# picobug.net
KiCad netlist of a schematic drawn in EasyEDA Pro
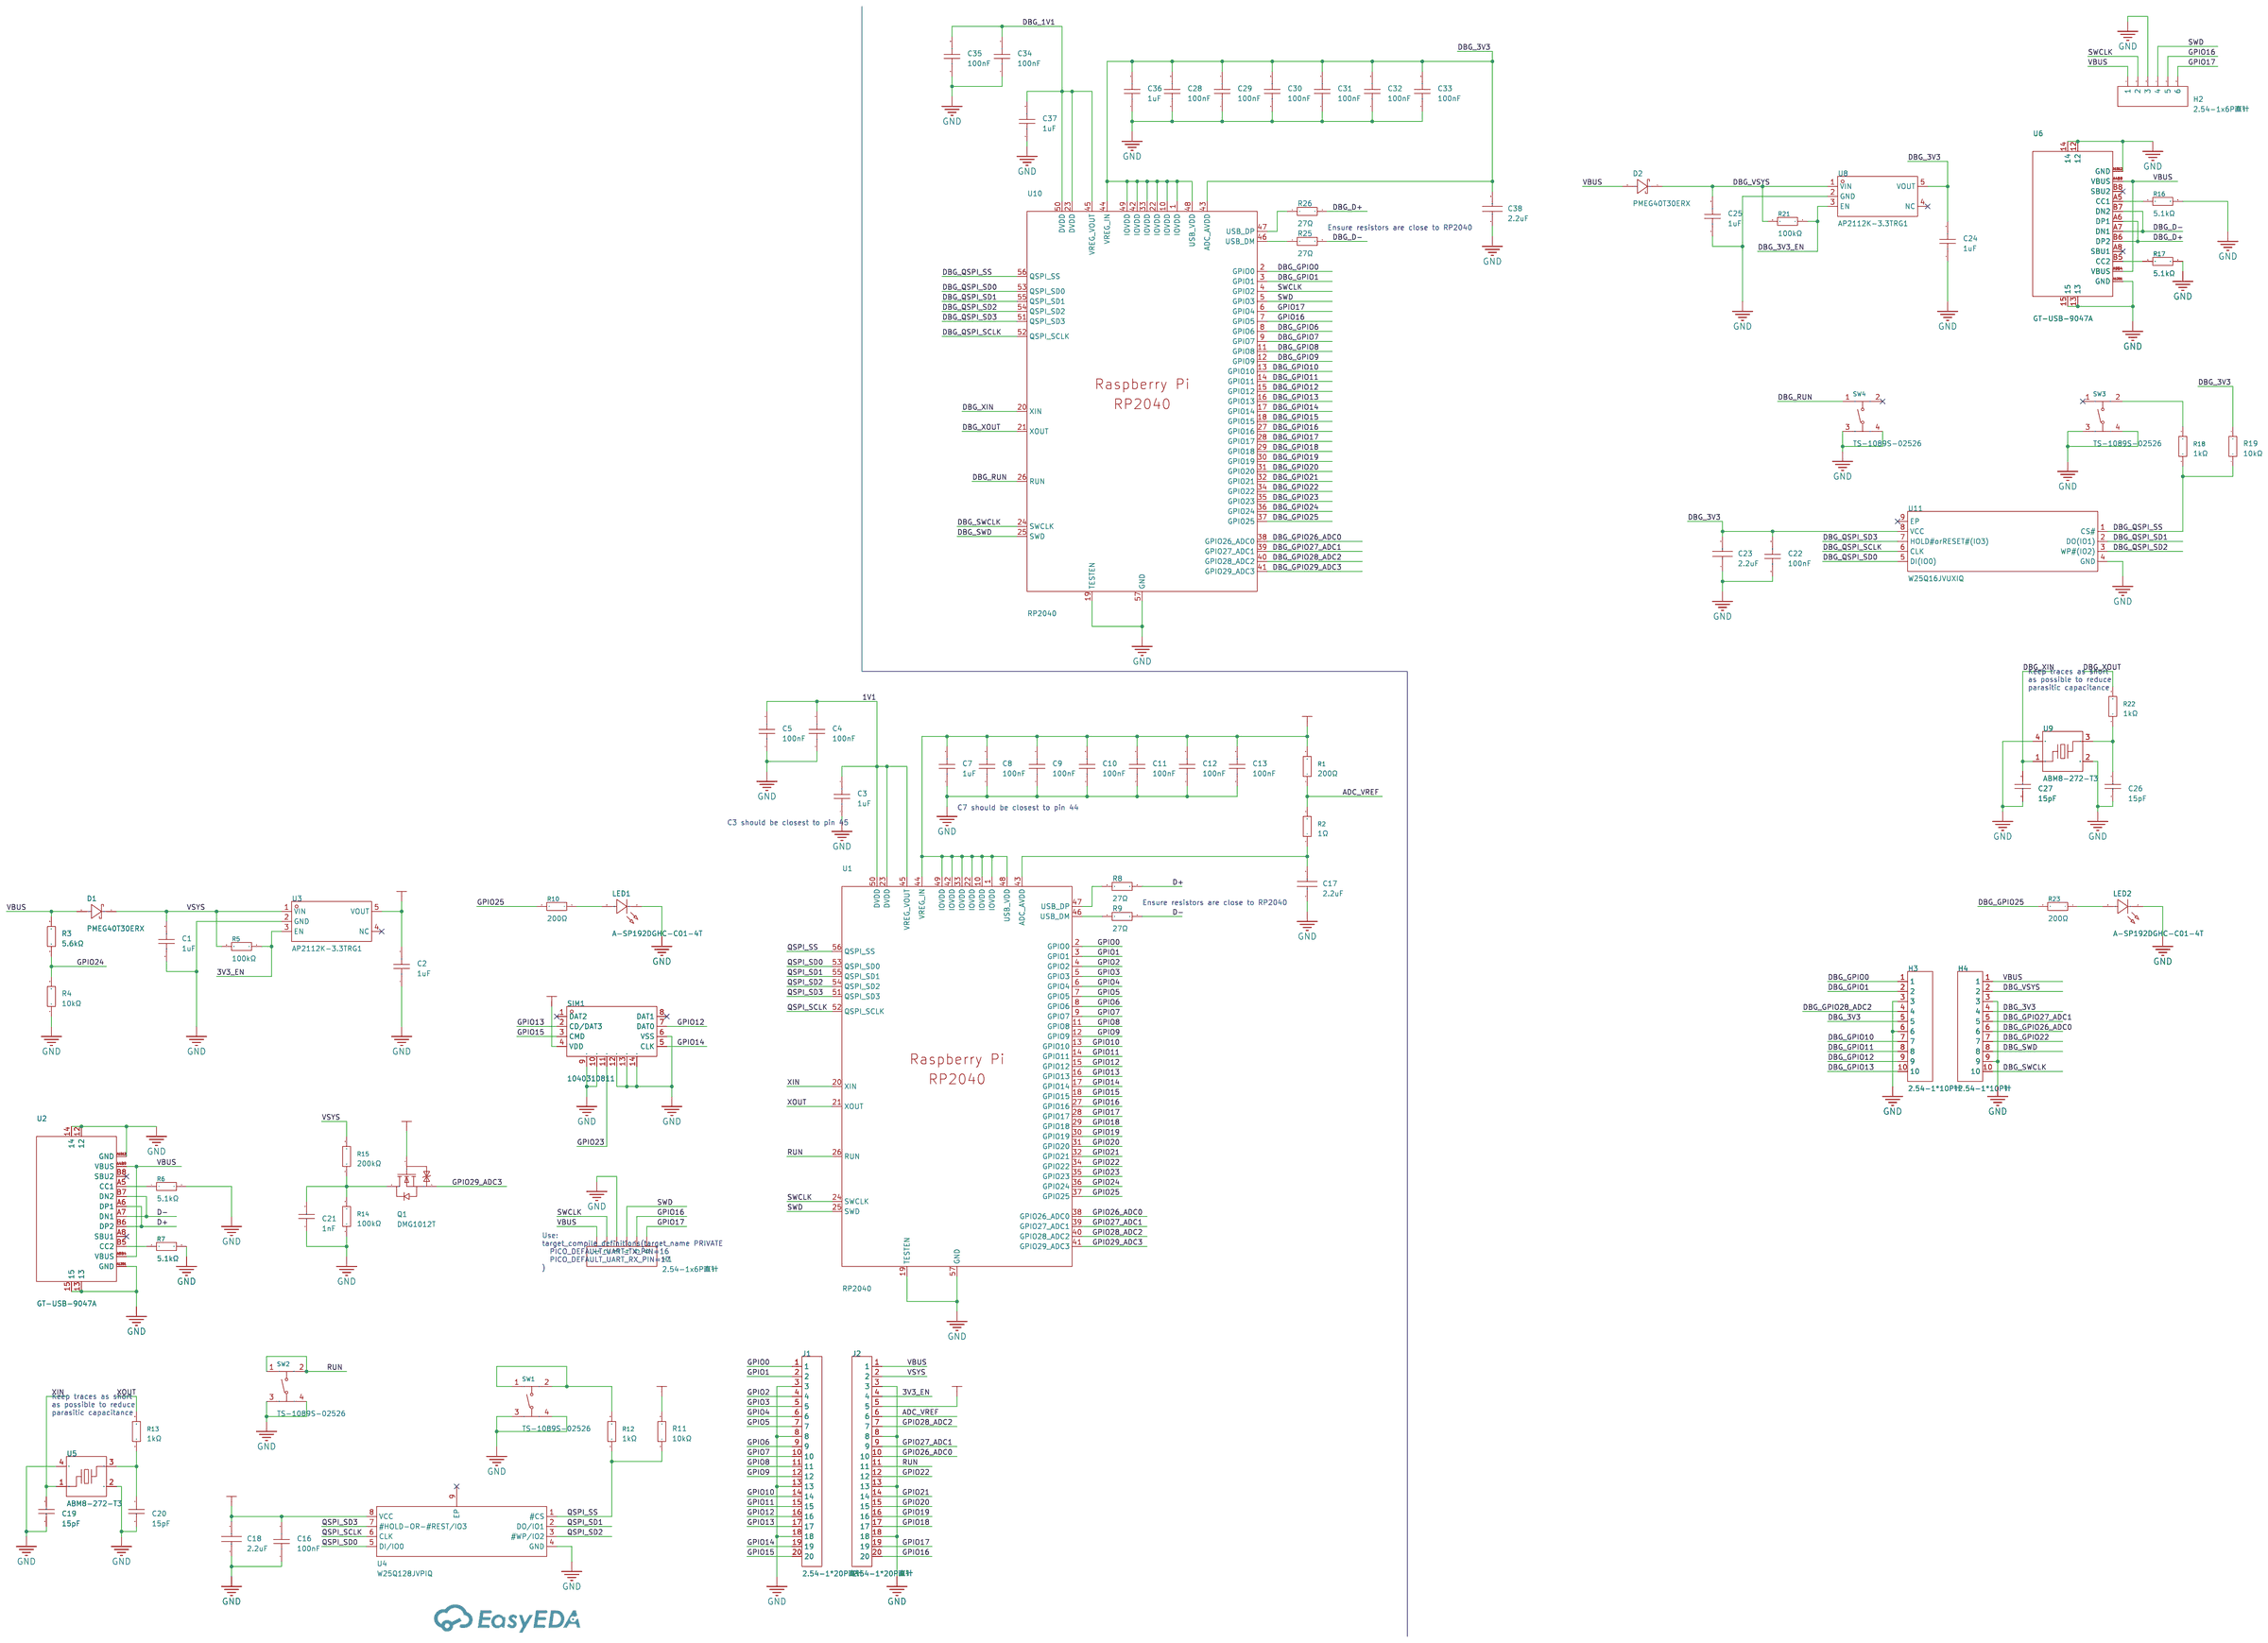
[diagram p0: schematic sheet]

(export (version "E")
  (design (tool "Eeschema 10.0.6"))
  (components
    (comp (ref "C1")
      (value "1uF")
      (footprint "easyedapro:C0402")
      (fields
        (field (name "Manufacturer Part") "CL05A105KA5NQNC")
        (field (name "Manufacturer") "SAMSUNG(三星)")
      )
      (libsource (lib "easyedapro") (part "CL05A105KA5NQNC"))
    )
    (comp (ref "C2")
      (value "1uF")
      (footprint "easyedapro:C0402")
      (fields
        (field (name "Manufacturer Part") "CL05A105KA5NQNC")
        (field (name "Manufacturer") "SAMSUNG(三星)")
      )
      (libsource (lib "easyedapro") (part "CL05A105KA5NQNC"))
    )
    (comp (ref "C3")
      (value "1uF")
      (footprint "easyedapro:C0402")
      (fields
        (field (name "Manufacturer Part") "CL05A105KA5NQNC")
        (field (name "Manufacturer") "SAMSUNG(三星)")
      )
      (libsource (lib "easyedapro") (part "CL05A105KA5NQNC"))
    )
    (comp (ref "C4")
      (value "100nF")
      (footprint "easyedapro:C0402")
      (fields
        (field (name "Manufacturer Part") "CL05B104KO5NNNC")
        (field (name "Manufacturer") "SAMSUNG(三星)")
      )
      (libsource (lib "easyedapro") (part "CL05B104KO5NNNC"))
    )
    (comp (ref "C5")
      (value "100nF")
      (footprint "easyedapro:C0402")
      (fields
        (field (name "Manufacturer Part") "CL05B104KO5NNNC")
        (field (name "Manufacturer") "SAMSUNG(三星)")
      )
      (libsource (lib "easyedapro") (part "CL05B104KO5NNNC"))
    )
    (comp (ref "C7")
      (value "1uF")
      (footprint "easyedapro:C0402")
      (fields
        (field (name "Manufacturer Part") "CL05A105KA5NQNC")
        (field (name "Manufacturer") "SAMSUNG(三星)")
      )
      (libsource (lib "easyedapro") (part "CL05A105KA5NQNC"))
    )
    (comp (ref "C8")
      (value "100nF")
      (footprint "easyedapro:C0402")
      (fields
        (field (name "Manufacturer Part") "CL05B104KO5NNNC")
        (field (name "Manufacturer") "SAMSUNG(三星)")
      )
      (libsource (lib "easyedapro") (part "CL05B104KO5NNNC"))
    )
    (comp (ref "C9")
      (value "100nF")
      (footprint "easyedapro:C0402")
      (fields
        (field (name "Manufacturer Part") "CL05B104KO5NNNC")
        (field (name "Manufacturer") "SAMSUNG(三星)")
      )
      (libsource (lib "easyedapro") (part "CL05B104KO5NNNC"))
    )
    (comp (ref "C10")
      (value "100nF")
      (footprint "easyedapro:C0402")
      (fields
        (field (name "Manufacturer Part") "CL05B104KO5NNNC")
        (field (name "Manufacturer") "SAMSUNG(三星)")
      )
      (libsource (lib "easyedapro") (part "CL05B104KO5NNNC"))
    )
    (comp (ref "C11")
      (value "100nF")
      (footprint "easyedapro:C0402")
      (fields
        (field (name "Manufacturer Part") "CL05B104KO5NNNC")
        (field (name "Manufacturer") "SAMSUNG(三星)")
      )
      (libsource (lib "easyedapro") (part "CL05B104KO5NNNC"))
    )
    (comp (ref "C12")
      (value "100nF")
      (footprint "easyedapro:C0402")
      (fields
        (field (name "Manufacturer Part") "CL05B104KO5NNNC")
        (field (name "Manufacturer") "SAMSUNG(三星)")
      )
      (libsource (lib "easyedapro") (part "CL05B104KO5NNNC"))
    )
    (comp (ref "C13")
      (value "100nF")
      (footprint "easyedapro:C0402")
      (fields
        (field (name "Manufacturer Part") "CL05B104KO5NNNC")
        (field (name "Manufacturer") "SAMSUNG(三星)")
      )
      (libsource (lib "easyedapro") (part "CL05B104KO5NNNC"))
    )
    (comp (ref "C16")
      (value "100nF")
      (footprint "easyedapro:C0402")
      (fields
        (field (name "Manufacturer Part") "CL05B104KO5NNNC")
        (field (name "Manufacturer") "SAMSUNG(三星)")
      )
      (libsource (lib "easyedapro") (part "CL05B104KO5NNNC"))
    )
    (comp (ref "C17")
      (value "2.2uF")
      (footprint "easyedapro:C0402")
      (fields
        (field (name "Manufacturer Part") "CL05A225MQ5NSNC")
        (field (name "Manufacturer") "SAMSUNG(三星)")
      )
      (libsource (lib "easyedapro") (part "CL05A225MQ5NSNC"))
    )
    (comp (ref "C18")
      (value "2.2uF")
      (footprint "easyedapro:C0402")
      (fields
        (field (name "Manufacturer Part") "CL05A225MQ5NSNC")
        (field (name "Manufacturer") "SAMSUNG(三星)")
      )
      (libsource (lib "easyedapro") (part "CL05A225MQ5NSNC"))
    )
    (comp (ref "C19")
      (value "15pF")
      (footprint "easyedapro:C0402")
      (fields (field (name "Manufacturer Part") "0402CG150J500NT") (field (name "Manufacturer") "FH(风华)"))
      (libsource (lib "easyedapro") (part "0402CG150J500NT"))
    )
    (comp (ref "C20")
      (value "15pF")
      (footprint "easyedapro:C0402")
      (fields (field (name "Manufacturer Part") "0402CG150J500NT") (field (name "Manufacturer") "FH(风华)"))
      (libsource (lib "easyedapro") (part "0402CG150J500NT"))
    )
    (comp (ref "C21")
      (value "1nF")
      (footprint "easyedapro:C0402")
      (fields (field (name "Manufacturer Part") "0402B102K500NT") (field (name "Manufacturer") "FH(风华)"))
      (libsource (lib "easyedapro") (part "0402B102K500NT"))
    )
    (comp (ref "C22")
      (value "100nF")
      (footprint "easyedapro:C0402")
      (fields
        (field (name "Manufacturer Part") "CL05B104KO5NNNC")
        (field (name "Manufacturer") "SAMSUNG(三星)")
      )
      (libsource (lib "easyedapro") (part "CL05B104KO5NNNC"))
    )
    (comp (ref "C23")
      (value "2.2uF")
      (footprint "easyedapro:C0402")
      (fields
        (field (name "Manufacturer Part") "CL05A225MQ5NSNC")
        (field (name "Manufacturer") "SAMSUNG(三星)")
      )
      (libsource (lib "easyedapro") (part "CL05A225MQ5NSNC"))
    )
    (comp (ref "C24")
      (value "1uF")
      (footprint "easyedapro:C0402")
      (fields
        (field (name "Manufacturer Part") "CL05A105KA5NQNC")
        (field (name "Manufacturer") "SAMSUNG(三星)")
      )
      (libsource (lib "easyedapro") (part "CL05A105KA5NQNC"))
    )
    (comp (ref "C25")
      (value "1uF")
      (footprint "easyedapro:C0402")
      (fields
        (field (name "Manufacturer Part") "CL05A105KA5NQNC")
        (field (name "Manufacturer") "SAMSUNG(三星)")
      )
      (libsource (lib "easyedapro") (part "CL05A105KA5NQNC"))
    )
    (comp (ref "C26")
      (value "15pF")
      (footprint "easyedapro:C0402")
      (fields (field (name "Manufacturer Part") "0402CG150J500NT") (field (name "Manufacturer") "FH(风华)"))
      (libsource (lib "easyedapro") (part "0402CG150J500NT"))
    )
    (comp (ref "C27")
      (value "15pF")
      (footprint "easyedapro:C0402")
      (fields (field (name "Manufacturer Part") "0402CG150J500NT") (field (name "Manufacturer") "FH(风华)"))
      (libsource (lib "easyedapro") (part "0402CG150J500NT"))
    )
    (comp (ref "C28")
      (value "100nF")
      (footprint "easyedapro:C0402")
      (fields
        (field (name "Manufacturer Part") "CL05B104KO5NNNC")
        (field (name "Manufacturer") "SAMSUNG(三星)")
      )
      (libsource (lib "easyedapro") (part "CL05B104KO5NNNC"))
    )
    (comp (ref "C29")
      (value "100nF")
      (footprint "easyedapro:C0402")
      (fields
        (field (name "Manufacturer Part") "CL05B104KO5NNNC")
        (field (name "Manufacturer") "SAMSUNG(三星)")
      )
      (libsource (lib "easyedapro") (part "CL05B104KO5NNNC"))
    )
    (comp (ref "C30")
      (value "100nF")
      (footprint "easyedapro:C0402")
      (fields
        (field (name "Manufacturer Part") "CL05B104KO5NNNC")
        (field (name "Manufacturer") "SAMSUNG(三星)")
      )
      (libsource (lib "easyedapro") (part "CL05B104KO5NNNC"))
    )
    (comp (ref "C31")
      (value "100nF")
      (footprint "easyedapro:C0402")
      (fields
        (field (name "Manufacturer Part") "CL05B104KO5NNNC")
        (field (name "Manufacturer") "SAMSUNG(三星)")
      )
      (libsource (lib "easyedapro") (part "CL05B104KO5NNNC"))
    )
    (comp (ref "C32")
      (value "100nF")
      (footprint "easyedapro:C0402")
      (fields
        (field (name "Manufacturer Part") "CL05B104KO5NNNC")
        (field (name "Manufacturer") "SAMSUNG(三星)")
      )
      (libsource (lib "easyedapro") (part "CL05B104KO5NNNC"))
    )
    (comp (ref "C33")
      (value "100nF")
      (footprint "easyedapro:C0402")
      (fields
        (field (name "Manufacturer Part") "CL05B104KO5NNNC")
        (field (name "Manufacturer") "SAMSUNG(三星)")
      )
      (libsource (lib "easyedapro") (part "CL05B104KO5NNNC"))
    )
    (comp (ref "C34")
      (value "100nF")
      (footprint "easyedapro:C0402")
      (fields
        (field (name "Manufacturer Part") "CL05B104KO5NNNC")
        (field (name "Manufacturer") "SAMSUNG(三星)")
      )
      (libsource (lib "easyedapro") (part "CL05B104KO5NNNC"))
    )
    (comp (ref "C35")
      (value "100nF")
      (footprint "easyedapro:C0402")
      (fields
        (field (name "Manufacturer Part") "CL05B104KO5NNNC")
        (field (name "Manufacturer") "SAMSUNG(三星)")
      )
      (libsource (lib "easyedapro") (part "CL05B104KO5NNNC"))
    )
    (comp (ref "C36")
      (value "1uF")
      (footprint "easyedapro:C0402")
      (fields
        (field (name "Manufacturer Part") "CL05A105KA5NQNC")
        (field (name "Manufacturer") "SAMSUNG(三星)")
      )
      (libsource (lib "easyedapro") (part "CL05A105KA5NQNC"))
    )
    (comp (ref "C37")
      (value "1uF")
      (footprint "easyedapro:C0402")
      (fields
        (field (name "Manufacturer Part") "CL05A105KA5NQNC")
        (field (name "Manufacturer") "SAMSUNG(三星)")
      )
      (libsource (lib "easyedapro") (part "CL05A105KA5NQNC"))
    )
    (comp (ref "C38")
      (value "2.2uF")
      (footprint "easyedapro:C0402")
      (fields
        (field (name "Manufacturer Part") "CL05A225MQ5NSNC")
        (field (name "Manufacturer") "SAMSUNG(三星)")
      )
      (libsource (lib "easyedapro") (part "CL05A225MQ5NSNC"))
    )
    (comp (ref "D1")
      (value "PMEG40T30ERX")
      (footprint "easyedapro:SOD-123W_L2.8-W1.8-LS3.7-RD")
      (fields (field (name "Manufacturer") "Nexperia(安世)"))
      (libsource (lib "easyedapro") (part "PMEG40T30ERX"))
    )
    (comp (ref "D2")
      (value "PMEG40T30ERX")
      (footprint "easyedapro:SOD-123W_L2.8-W1.8-LS3.7-RD")
      (fields (field (name "Manufacturer") "Nexperia(安世)"))
      (libsource (lib "easyedapro") (part "PMEG40T30ERX"))
    )
    (comp (ref "H1")
      (value "2.54-1x6P直针")
      (footprint "easyedapro:HDR-TH_6P-P2.54-V-M-1")
      (fields (field (name "Manufacturer") "BOOMELE(博穆精密)"))
      (libsource (lib "easyedapro") (part "Header-Male-2.54_1x6"))
    )
    (comp (ref "H2")
      (value "2.54-1x6P直针")
      (footprint "easyedapro:HDR-TH_6P-P2.54-V-M-1")
      (fields (field (name "Manufacturer") "BOOMELE(博穆精密)"))
      (libsource (lib "easyedapro") (part "Header-Male-2.54_1x6"))
    )
    (comp (ref "H3")
      (value "2.54-1*10P针")
      (footprint "easyedapro:HDR-TH_10P-P2.54-V-M-1")
      (fields (field (name "Manufacturer") "BOOMELE(博穆精密)"))
      (libsource (lib "easyedapro") (part "Header-Male-2.54_1x10"))
    )
    (comp (ref "H4")
      (value "2.54-1*10P针")
      (footprint "easyedapro:HDR-TH_10P-P2.54-V-M-1")
      (fields (field (name "Manufacturer") "BOOMELE(博穆精密)"))
      (libsource (lib "easyedapro") (part "Header-Male-2.54_1x10"))
    )
    (comp (ref "J1")
      (value "2.54-1*20P直针")
      (footprint "easyedapro:HDR-TH_20P-P2.54-V-M-1")
      (fields (field (name "Manufacturer") "BOOMELE(博穆精密)"))
      (libsource (lib "easyedapro") (part "Header-Male-2.54_1x20"))
    )
    (comp (ref "J2")
      (value "2.54-1*20P直针")
      (footprint "easyedapro:HDR-TH_20P-P2.54-V-M-1")
      (fields (field (name "Manufacturer") "BOOMELE(博穆精密)"))
      (libsource (lib "easyedapro") (part "Header-Male-2.54_1x20"))
    )
    (comp (ref "LED1")
      (value "A-SP192DGHC-C01-4T")
      (footprint "easyedapro:LED0603-FD")
      (fields (field (name "Manufacturer") "Amicc(欧密格光电)"))
      (libsource (lib "easyedapro") (part "A-SP192DGHC-C01-4T"))
    )
    (comp (ref "LED2")
      (value "A-SP192DGHC-C01-4T")
      (footprint "easyedapro:LED0603-FD")
      (fields (field (name "Manufacturer") "Amicc(欧密格光电)"))
      (libsource (lib "easyedapro") (part "A-SP192DGHC-C01-4T"))
    )
    (comp (ref "Q1")
      (value "DMG1012T")
      (footprint "easyedapro:SOT-523-3_L1.6-W0.8-P1.00-LS1.6-BR")
      (fields (field (name "Manufacturer") "TECH PUBLIC(台舟)"))
      (libsource (lib "easyedapro") (part "DMG1012T_C2830301"))
    )
    (comp (ref "R1")
      (value "200Ω")
      (footprint "easyedapro:R0402")
      (fields
        (field (name "Manufacturer Part") "0402WGF2000TCE")
        (field (name "Manufacturer") "UNI-ROYAL(厚声)")
      )
      (libsource (lib "easyedapro") (part "0402WGF2000TCE"))
    )
    (comp (ref "R2")
      (value "1Ω")
      (footprint "easyedapro:R0603")
      (fields
        (field (name "Manufacturer Part") "0603WAF100KT5E")
        (field (name "Manufacturer") "UNI-ROYAL(厚声)")
      )
      (libsource (lib "easyedapro") (part "0603WAF100KT5E"))
    )
    (comp (ref "R3")
      (value "5.6kΩ")
      (footprint "easyedapro:R0402")
      (fields
        (field (name "Manufacturer Part") "0402WGF5601TCE")
        (field (name "Manufacturer") "UNI-ROYAL(厚声)")
      )
      (libsource (lib "easyedapro") (part "0402WGF5601TCE"))
    )
    (comp (ref "R4")
      (value "10kΩ")
      (footprint "easyedapro:R0402")
      (fields
        (field (name "Manufacturer Part") "0402WGF1002TCE")
        (field (name "Manufacturer") "UNI-ROYAL(厚声)")
      )
      (libsource (lib "easyedapro") (part "0402WGF1002TCE"))
    )
    (comp (ref "R5")
      (value "100kΩ")
      (footprint "easyedapro:R0402")
      (fields
        (field (name "Manufacturer Part") "0402WGF1003TCE")
        (field (name "Manufacturer") "UNI-ROYAL(厚声)")
      )
      (libsource (lib "easyedapro") (part "0402WGF1003TCE"))
    )
    (comp (ref "R6")
      (value "5.1kΩ")
      (footprint "easyedapro:R0402")
      (fields
        (field (name "Manufacturer Part") "0402WGF5101TCE")
        (field (name "Manufacturer") "UNI-ROYAL(厚声)")
      )
      (libsource (lib "easyedapro") (part "0402WGF5101TCE"))
    )
    (comp (ref "R7")
      (value "5.1kΩ")
      (footprint "easyedapro:R0402")
      (fields
        (field (name "Manufacturer Part") "0402WGF5101TCE")
        (field (name "Manufacturer") "UNI-ROYAL(厚声)")
      )
      (libsource (lib "easyedapro") (part "0402WGF5101TCE"))
    )
    (comp (ref "R8")
      (value "27Ω")
      (footprint "easyedapro:R0402")
      (fields (field (name "Manufacturer Part") "RC0402FR-0727RL") (field (name "Manufacturer") "YAGEO(国巨)"))
      (libsource (lib "easyedapro") (part "RC0402FR-0727RL"))
    )
    (comp (ref "R9")
      (value "27Ω")
      (footprint "easyedapro:R0402")
      (fields (field (name "Manufacturer Part") "RC0402FR-0727RL") (field (name "Manufacturer") "YAGEO(国巨)"))
      (libsource (lib "easyedapro") (part "RC0402FR-0727RL"))
    )
    (comp (ref "R10")
      (value "200Ω")
      (footprint "easyedapro:R0402")
      (fields
        (field (name "Manufacturer Part") "0402WGF2000TCE")
        (field (name "Manufacturer") "UNI-ROYAL(厚声)")
      )
      (libsource (lib "easyedapro") (part "0402WGF2000TCE"))
    )
    (comp (ref "R11")
      (value "10kΩ")
      (footprint "easyedapro:R0402")
      (fields
        (field (name "Manufacturer Part") "0402WGF1002TCE")
        (field (name "Manufacturer") "UNI-ROYAL(厚声)")
      )
      (libsource (lib "easyedapro") (part "0402WGF1002TCE"))
    )
    (comp (ref "R12")
      (value "1kΩ")
      (footprint "easyedapro:R0402")
      (fields
        (field (name "Manufacturer Part") "0402WGF1001TCE")
        (field (name "Manufacturer") "UNI-ROYAL(厚声)")
      )
      (libsource (lib "easyedapro") (part "0402WGF1001TCE"))
    )
    (comp (ref "R13")
      (value "1kΩ")
      (footprint "easyedapro:R0402")
      (fields
        (field (name "Manufacturer Part") "0402WGF1001TCE")
        (field (name "Manufacturer") "UNI-ROYAL(厚声)")
      )
      (libsource (lib "easyedapro") (part "0402WGF1001TCE"))
    )
    (comp (ref "R14")
      (value "100kΩ")
      (footprint "easyedapro:R0402")
      (fields
        (field (name "Manufacturer Part") "0402WGF1003TCE")
        (field (name "Manufacturer") "UNI-ROYAL(厚声)")
      )
      (libsource (lib "easyedapro") (part "0402WGF1003TCE"))
    )
    (comp (ref "R15")
      (value "200kΩ")
      (footprint "easyedapro:R0402")
      (fields
        (field (name "Manufacturer Part") "0402WGF2003TCE")
        (field (name "Manufacturer") "UNI-ROYAL(厚声)")
      )
      (libsource (lib "easyedapro") (part "0402WGF2003TCE"))
    )
    (comp (ref "R16")
      (value "5.1kΩ")
      (footprint "easyedapro:R0402")
      (fields
        (field (name "Manufacturer Part") "0402WGF5101TCE")
        (field (name "Manufacturer") "UNI-ROYAL(厚声)")
      )
      (libsource (lib "easyedapro") (part "0402WGF5101TCE"))
    )
    (comp (ref "R17")
      (value "5.1kΩ")
      (footprint "easyedapro:R0402")
      (fields
        (field (name "Manufacturer Part") "0402WGF5101TCE")
        (field (name "Manufacturer") "UNI-ROYAL(厚声)")
      )
      (libsource (lib "easyedapro") (part "0402WGF5101TCE"))
    )
    (comp (ref "R18")
      (value "1kΩ")
      (footprint "easyedapro:R0402")
      (fields
        (field (name "Manufacturer Part") "0402WGF1001TCE")
        (field (name "Manufacturer") "UNI-ROYAL(厚声)")
      )
      (libsource (lib "easyedapro") (part "0402WGF1001TCE"))
    )
    (comp (ref "R19")
      (value "10kΩ")
      (footprint "easyedapro:R0402")
      (fields
        (field (name "Manufacturer Part") "0402WGF1002TCE")
        (field (name "Manufacturer") "UNI-ROYAL(厚声)")
      )
      (libsource (lib "easyedapro") (part "0402WGF1002TCE"))
    )
    (comp (ref "R21")
      (value "100kΩ")
      (footprint "easyedapro:R0402")
      (fields
        (field (name "Manufacturer Part") "0402WGF1003TCE")
        (field (name "Manufacturer") "UNI-ROYAL(厚声)")
      )
      (libsource (lib "easyedapro") (part "0402WGF1003TCE"))
    )
    (comp (ref "R22")
      (value "1kΩ")
      (footprint "easyedapro:R0402")
      (fields
        (field (name "Manufacturer Part") "0402WGF1001TCE")
        (field (name "Manufacturer") "UNI-ROYAL(厚声)")
      )
      (libsource (lib "easyedapro") (part "0402WGF1001TCE"))
    )
    (comp (ref "R23")
      (value "200Ω")
      (footprint "easyedapro:R0402")
      (fields
        (field (name "Manufacturer Part") "0402WGF2000TCE")
        (field (name "Manufacturer") "UNI-ROYAL(厚声)")
      )
      (libsource (lib "easyedapro") (part "0402WGF2000TCE"))
    )
    (comp (ref "R25")
      (value "27Ω")
      (footprint "easyedapro:R0402")
      (fields (field (name "Manufacturer Part") "RC0402FR-0727RL") (field (name "Manufacturer") "YAGEO(国巨)"))
      (libsource (lib "easyedapro") (part "RC0402FR-0727RL"))
    )
    (comp (ref "R26")
      (value "27Ω")
      (footprint "easyedapro:R0402")
      (fields (field (name "Manufacturer Part") "RC0402FR-0727RL") (field (name "Manufacturer") "YAGEO(国巨)"))
      (libsource (lib "easyedapro") (part "RC0402FR-0727RL"))
    )
    (comp (ref "SIM1")
      (value "1040310811")
      (footprint "easyedapro:SIM-SMD_8P-1040310811")
      (fields (field (name "Manufacturer") "MOLEX"))
      (libsource (lib "easyedapro") (part "1040310811"))
    )
    (comp (ref "SW1")
      (value "TS-1089S-02526")
      (footprint "easyedapro:SW-SMD_4P-L4.2-W3.3-P2.15-LS5.1")
      (fields (field (name "Manufacturer") "XUNPU(讯普)"))
      (libsource (lib "easyedapro") (part "TS-1089S-02526"))
    )
    (comp (ref "SW2")
      (value "TS-1089S-02526")
      (footprint "easyedapro:SW-SMD_4P-L4.2-W3.3-P2.15-LS5.1")
      (fields (field (name "Manufacturer") "XUNPU(讯普)"))
      (libsource (lib "easyedapro") (part "TS-1089S-02526"))
    )
    (comp (ref "SW3")
      (value "TS-1089S-02526")
      (footprint "easyedapro:SW-SMD_4P-L4.2-W3.3-P2.15-LS5.1")
      (fields (field (name "Manufacturer") "XUNPU(讯普)"))
      (libsource (lib "easyedapro") (part "TS-1089S-02526"))
    )
    (comp (ref "SW4")
      (value "TS-1089S-02526")
      (footprint "easyedapro:SW-SMD_4P-L4.2-W3.3-P2.15-LS5.1")
      (fields (field (name "Manufacturer") "XUNPU(讯普)"))
      (libsource (lib "easyedapro") (part "TS-1089S-02526"))
    )
    (comp (ref "U1")
      (value "RP2040")
      (footprint "easyedapro:LQFN-56_L7.0-W7.0-P0.4-EP")
      (description "CPU Core:- CPU Maximum Speed:133MHz Number of I/O:30 ADC (Bit):12bit Applications:-")
      (fields (field (name "Manufacturer") "Raspberry Pi(树莓派)"))
      (libsource (lib "easyedapro") (part "RP2040"))
    )
    (comp (ref "U2")
      (value "GT-USB-9047A")
      (footprint "easyedapro:USB-C-SMD_GT-USB-9047A")
      (fields (field (name "Manufacturer") "G-Switch(品赞)"))
      (libsource (lib "easyedapro") (part "GT-USB-9047A"))
    )
    (comp (ref "U3")
      (value "AP2112K-3.3TRG1")
      (footprint "easyedapro:SOT-25-5_L2.9-W1.6-P0.95-LS2.8-BL")
      (fields (field (name "Manufacturer") "DIODES(美台)"))
      (libsource (lib "easyedapro") (part "AP2112K-3.3TRG1"))
    )
    (comp (ref "U4")
      (value "W25Q128JVPIQ")
      (footprint "easyedapro:WSON-8_L6.0-W5.0-P1.27-BL-EP")
      (fields (field (name "Manufacturer") "Winbond(华邦)"))
      (libsource (lib "easyedapro") (part "W25Q128JVPIQTR"))
    )
    (comp (ref "U5")
      (value "ABM8-272-T3")
      (footprint "easyedapro:CRYSTAL-SMD_4P-L3.2-W2.5-BL")
      (fields (field (name "Manufacturer") "ABRACON"))
      (libsource (lib "easyedapro") (part "ABM8-272-T3_C20625731"))
    )
    (comp (ref "U6")
      (value "GT-USB-9047A")
      (footprint "easyedapro:USB-C-SMD_GT-USB-9047A")
      (fields (field (name "Manufacturer") "G-Switch(品赞)"))
      (libsource (lib "easyedapro") (part "GT-USB-9047A"))
    )
    (comp (ref "U8")
      (value "AP2112K-3.3TRG1")
      (footprint "easyedapro:SOT-25-5_L2.9-W1.6-P0.95-LS2.8-BL")
      (fields (field (name "Manufacturer") "DIODES(美台)"))
      (libsource (lib "easyedapro") (part "AP2112K-3.3TRG1"))
    )
    (comp (ref "U9")
      (value "ABM8-272-T3")
      (footprint "easyedapro:CRYSTAL-SMD_4P-L3.2-W2.5-BL")
      (fields (field (name "Manufacturer") "ABRACON"))
      (libsource (lib "easyedapro") (part "ABM8-272-T3_C20625731"))
    )
    (comp (ref "U10")
      (value "RP2040")
      (footprint "easyedapro:LQFN-56_L7.0-W7.0-P0.4-EP")
      (description "CPU Core:- CPU Maximum Speed:133MHz Number of I/O:30 ADC (Bit):12bit Applications:-")
      (fields (field (name "Manufacturer") "Raspberry Pi(树莓派)"))
      (libsource (lib "easyedapro") (part "RP2040"))
    )
    (comp (ref "U11")
      (value "W25Q16JVUXIQ")
      (footprint "easyedapro:USON-8_L3.0-W2.0-P0.50-BL-EP")
      (fields (field (name "Manufacturer") "Winbond(华邦)"))
      (libsource (lib "easyedapro") (part "W25Q16JVUXIQ"))
    )
  )
  (nets
    (net (code "1") (name "/1V1") (class "Default")
      (node (ref "C3") (pin "2") (pinfunction "2_2") (pintype "unspecified"))
      (node (ref "C4") (pin "2") (pinfunction "2_2") (pintype "unspecified"))
      (node (ref "C5") (pin "2") (pinfunction "2_2") (pintype "unspecified"))
      (node (ref "U1") (pin "23") (pinfunction "DVDD_23") (pintype "bidirectional"))
      (node (ref "U1") (pin "45") (pinfunction "VREG_VOUT_45") (pintype "bidirectional"))
      (node (ref "U1") (pin "50") (pinfunction "DVDD_50") (pintype "bidirectional"))
    )
    (net (code "2") (name "/3V3_EN") (class "Default")
      (node (ref "J2") (pin "4") (pinfunction "4_4") (pintype "unspecified"))
      (node (ref "R5") (pin "1") (pinfunction "1_1") (pintype "input"))
      (node (ref "U3") (pin "3") (pinfunction "EN_3") (pintype "unspecified"))
    )
    (net (code "3") (name "/ADC_VREF") (class "Default")
      (node (ref "J2") (pin "6") (pinfunction "6_6") (pintype "unspecified"))
      (node (ref "R1") (pin "1") (pinfunction "1_1") (pintype "input"))
      (node (ref "R2") (pin "2") (pinfunction "2_2") (pintype "input"))
    )
    (net (code "4") (name "/D+") (class "Default")
      (node (ref "R8") (pin "2") (pinfunction "2_2") (pintype "input"))
      (node (ref "U2") (pin "A6") (pinfunction "DP1_A6") (pintype "unspecified"))
      (node (ref "U2") (pin "B6") (pinfunction "DP2_B6") (pintype "unspecified"))
    )
    (net (code "5") (name "/D-") (class "Default")
      (node (ref "R9") (pin "2") (pinfunction "2_2") (pintype "input"))
      (node (ref "U2") (pin "A7") (pinfunction "DN1_A7") (pintype "unspecified"))
      (node (ref "U2") (pin "B7") (pinfunction "DN2_B7") (pintype "unspecified"))
    )
    (net (code "6") (name "/DBG_1V1") (class "Default")
      (node (ref "C34") (pin "2") (pinfunction "2_2") (pintype "unspecified"))
      (node (ref "C35") (pin "2") (pinfunction "2_2") (pintype "unspecified"))
      (node (ref "C37") (pin "2") (pinfunction "2_2") (pintype "unspecified"))
      (node (ref "U10") (pin "23") (pinfunction "DVDD_23") (pintype "bidirectional"))
      (node (ref "U10") (pin "45") (pinfunction "VREG_VOUT_45") (pintype "bidirectional"))
      (node (ref "U10") (pin "50") (pinfunction "DVDD_50") (pintype "bidirectional"))
    )
    (net (code "7") (name "/DBG_3V3") (class "Default")
      (node (ref "C22") (pin "2") (pinfunction "2_2") (pintype "unspecified"))
      (node (ref "C23") (pin "2") (pinfunction "2_2") (pintype "unspecified"))
      (node (ref "C24") (pin "2") (pinfunction "2_2") (pintype "unspecified"))
      (node (ref "C28") (pin "2") (pinfunction "2_2") (pintype "unspecified"))
      (node (ref "C29") (pin "2") (pinfunction "2_2") (pintype "unspecified"))
      (node (ref "C30") (pin "2") (pinfunction "2_2") (pintype "unspecified"))
      (node (ref "C31") (pin "2") (pinfunction "2_2") (pintype "unspecified"))
      (node (ref "C32") (pin "2") (pinfunction "2_2") (pintype "unspecified"))
      (node (ref "C33") (pin "2") (pinfunction "2_2") (pintype "unspecified"))
      (node (ref "C36") (pin "2") (pinfunction "2_2") (pintype "unspecified"))
      (node (ref "C38") (pin "2") (pinfunction "2_2") (pintype "unspecified"))
      (node (ref "H3") (pin "5") (pinfunction "5_5") (pintype "unspecified"))
      (node (ref "H4") (pin "4") (pinfunction "4_4") (pintype "unspecified"))
      (node (ref "R19") (pin "2") (pinfunction "2_2") (pintype "input"))
      (node (ref "U10") (pin "1") (pinfunction "IOVDD_1") (pintype "bidirectional"))
      (node (ref "U10") (pin "10") (pinfunction "IOVDD_10") (pintype "bidirectional"))
      (node (ref "U10") (pin "22") (pinfunction "IOVDD_22") (pintype "bidirectional"))
      (node (ref "U10") (pin "33") (pinfunction "IOVDD_33") (pintype "bidirectional"))
      (node (ref "U10") (pin "42") (pinfunction "IOVDD_42") (pintype "bidirectional"))
      (node (ref "U10") (pin "43") (pinfunction "ADC_AVDD_43") (pintype "bidirectional"))
      (node (ref "U10") (pin "44") (pinfunction "VREG_IN_44") (pintype "bidirectional"))
      (node (ref "U10") (pin "48") (pinfunction "USB_VDD_48") (pintype "bidirectional"))
      (node (ref "U10") (pin "49") (pinfunction "IOVDD_49") (pintype "bidirectional"))
      (node (ref "U11") (pin "8") (pinfunction "VCC_8") (pintype "unspecified"))
      (node (ref "U8") (pin "5") (pinfunction "VOUT_5") (pintype "unspecified"))
    )
    (net (code "8") (name "/DBG_3V3_EN") (class "Default")
      (node (ref "R21") (pin "1") (pinfunction "1_1") (pintype "input"))
      (node (ref "U8") (pin "3") (pinfunction "EN_3") (pintype "unspecified"))
    )
    (net (code "9") (name "/DBG_D+") (class "Default")
      (node (ref "R26") (pin "2") (pinfunction "2_2") (pintype "input"))
      (node (ref "U6") (pin "A6") (pinfunction "DP1_A6") (pintype "unspecified"))
      (node (ref "U6") (pin "B6") (pinfunction "DP2_B6") (pintype "unspecified"))
    )
    (net (code "10") (name "/DBG_D-") (class "Default")
      (node (ref "R25") (pin "2") (pinfunction "2_2") (pintype "input"))
      (node (ref "U6") (pin "A7") (pinfunction "DN1_A7") (pintype "unspecified"))
      (node (ref "U6") (pin "B7") (pinfunction "DN2_B7") (pintype "unspecified"))
    )
    (net (code "11") (name "/DBG_GPIO0") (class "Default")
      (node (ref "H3") (pin "1") (pinfunction "1_1") (pintype "unspecified"))
      (node (ref "U10") (pin "2") (pinfunction "GPIO0_2") (pintype "bidirectional"))
    )
    (net (code "12") (name "/DBG_GPIO1") (class "Default")
      (node (ref "H3") (pin "2") (pinfunction "2_2") (pintype "unspecified"))
      (node (ref "U10") (pin "3") (pinfunction "GPIO1_3") (pintype "bidirectional"))
    )
    (net (code "13") (name "/DBG_GPIO6") (class "Default")
      (node (ref "U10") (pin "8") (pinfunction "GPIO6_8") (pintype "bidirectional"))
    )
    (net (code "14") (name "/DBG_GPIO7") (class "Default")
      (node (ref "U10") (pin "9") (pinfunction "GPIO7_9") (pintype "bidirectional"))
    )
    (net (code "15") (name "/DBG_GPIO8") (class "Default")
      (node (ref "U10") (pin "11") (pinfunction "GPIO8_11") (pintype "bidirectional"))
    )
    (net (code "16") (name "/DBG_GPIO9") (class "Default")
      (node (ref "U10") (pin "12") (pinfunction "GPIO9_12") (pintype "bidirectional"))
    )
    (net (code "17") (name "/DBG_GPIO10") (class "Default")
      (node (ref "H3") (pin "7") (pinfunction "7_7") (pintype "unspecified"))
      (node (ref "U10") (pin "13") (pinfunction "GPIO10_13") (pintype "bidirectional"))
    )
    (net (code "18") (name "/DBG_GPIO11") (class "Default")
      (node (ref "H3") (pin "8") (pinfunction "8_8") (pintype "unspecified"))
      (node (ref "U10") (pin "14") (pinfunction "GPIO11_14") (pintype "bidirectional"))
    )
    (net (code "19") (name "/DBG_GPIO12") (class "Default")
      (node (ref "H3") (pin "9") (pinfunction "9_9") (pintype "unspecified"))
      (node (ref "U10") (pin "15") (pinfunction "GPIO12_15") (pintype "bidirectional"))
    )
    (net (code "20") (name "/DBG_GPIO13") (class "Default")
      (node (ref "H3") (pin "10") (pinfunction "10_10") (pintype "unspecified"))
      (node (ref "U10") (pin "16") (pinfunction "GPIO13_16") (pintype "bidirectional"))
    )
    (net (code "21") (name "/DBG_GPIO14") (class "Default")
      (node (ref "U10") (pin "17") (pinfunction "GPIO14_17") (pintype "bidirectional"))
    )
    (net (code "22") (name "/DBG_GPIO15") (class "Default")
      (node (ref "U10") (pin "18") (pinfunction "GPIO15_18") (pintype "bidirectional"))
    )
    (net (code "23") (name "/DBG_GPIO16") (class "Default")
      (node (ref "U10") (pin "27") (pinfunction "GPIO16_27") (pintype "bidirectional"))
    )
    (net (code "24") (name "/DBG_GPIO17") (class "Default")
      (node (ref "U10") (pin "28") (pinfunction "GPIO17_28") (pintype "bidirectional"))
    )
    (net (code "25") (name "/DBG_GPIO18") (class "Default")
      (node (ref "U10") (pin "29") (pinfunction "GPIO18_29") (pintype "bidirectional"))
    )
    (net (code "26") (name "/DBG_GPIO19") (class "Default")
      (node (ref "U10") (pin "30") (pinfunction "GPIO19_30") (pintype "bidirectional"))
    )
    (net (code "27") (name "/DBG_GPIO20") (class "Default")
      (node (ref "U10") (pin "31") (pinfunction "GPIO20_31") (pintype "bidirectional"))
    )
    (net (code "28") (name "/DBG_GPIO21") (class "Default")
      (node (ref "U10") (pin "32") (pinfunction "GPIO21_32") (pintype "bidirectional"))
    )
    (net (code "29") (name "/DBG_GPIO22") (class "Default")
      (node (ref "H4") (pin "7") (pinfunction "7_7") (pintype "unspecified"))
      (node (ref "U10") (pin "34") (pinfunction "GPIO22_34") (pintype "bidirectional"))
    )
    (net (code "30") (name "/DBG_GPIO23") (class "Default")
      (node (ref "U10") (pin "35") (pinfunction "GPIO23_35") (pintype "bidirectional"))
    )
    (net (code "31") (name "/DBG_GPIO24") (class "Default")
      (node (ref "U10") (pin "36") (pinfunction "GPIO24_36") (pintype "bidirectional"))
    )
    (net (code "32") (name "/DBG_GPIO25") (class "Default")
      (node (ref "R23") (pin "2") (pinfunction "2_2") (pintype "input"))
      (node (ref "U10") (pin "37") (pinfunction "GPIO25_37") (pintype "bidirectional"))
    )
    (net (code "33") (name "/DBG_GPIO26_ADC0") (class "Default")
      (node (ref "H4") (pin "6") (pinfunction "6_6") (pintype "unspecified"))
      (node (ref "U10") (pin "38") (pinfunction "GPIO26_ADC0_38") (pintype "bidirectional"))
    )
    (net (code "34") (name "/DBG_GPIO27_ADC1") (class "Default")
      (node (ref "H4") (pin "5") (pinfunction "5_5") (pintype "unspecified"))
      (node (ref "U10") (pin "39") (pinfunction "GPIO27_ADC1_39") (pintype "bidirectional"))
    )
    (net (code "35") (name "/DBG_GPIO28_ADC2") (class "Default")
      (node (ref "H3") (pin "4") (pinfunction "4_4") (pintype "unspecified"))
      (node (ref "U10") (pin "40") (pinfunction "GPIO28_ADC2_40") (pintype "bidirectional"))
    )
    (net (code "36") (name "/DBG_GPIO29_ADC3") (class "Default")
      (node (ref "U10") (pin "41") (pinfunction "GPIO29_ADC3_41") (pintype "bidirectional"))
    )
    (net (code "37") (name "/DBG_QSPI_SCLK") (class "Default")
      (node (ref "U10") (pin "52") (pinfunction "QSPI_SCLK_52") (pintype "output"))
      (node (ref "U11") (pin "6") (pinfunction "CLK_6") (pintype "unspecified"))
    )
    (net (code "38") (name "/DBG_QSPI_SD0") (class "Default")
      (node (ref "U10") (pin "53") (pinfunction "QSPI_SD0_53") (pintype "bidirectional"))
      (node (ref "U11") (pin "5") (pinfunction "DI(IO0)_5") (pintype "unspecified"))
    )
    (net (code "39") (name "/DBG_QSPI_SD1") (class "Default")
      (node (ref "U10") (pin "55") (pinfunction "QSPI_SD1_55") (pintype "bidirectional"))
      (node (ref "U11") (pin "2") (pinfunction "DO(IO1)_2") (pintype "unspecified"))
    )
    (net (code "40") (name "/DBG_QSPI_SD2") (class "Default")
      (node (ref "U10") (pin "54") (pinfunction "QSPI_SD2_54") (pintype "bidirectional"))
      (node (ref "U11") (pin "3") (pinfunction "WP#(IO2)_3") (pintype "unspecified"))
    )
    (net (code "41") (name "/DBG_QSPI_SD3") (class "Default")
      (node (ref "U10") (pin "51") (pinfunction "QSPI_SD3_51") (pintype "bidirectional"))
      (node (ref "U11") (pin "7") (pinfunction "HOLD#orRESET#(IO3)_7") (pintype "unspecified"))
    )
    (net (code "42") (name "/DBG_QSPI_SS") (class "Default")
      (node (ref "R18") (pin "1") (pinfunction "1_1") (pintype "input"))
      (node (ref "R19") (pin "1") (pinfunction "1_1") (pintype "input"))
      (node (ref "U10") (pin "56") (pinfunction "QSPI_SS_56") (pintype "bidirectional"))
      (node (ref "U11") (pin "1") (pinfunction "CS#_1") (pintype "unspecified"))
    )
    (net (code "43") (name "/DBG_RUN") (class "Default")
      (node (ref "SW4") (pin "1") (pinfunction "1_1") (pintype "input"))
      (node (ref "U10") (pin "26") (pinfunction "RUN_26") (pintype "input"))
    )
    (net (code "44") (name "/DBG_SWCLK") (class "Default")
      (node (ref "H4") (pin "10") (pinfunction "10_10") (pintype "unspecified"))
      (node (ref "U10") (pin "24") (pinfunction "SWCLK_24") (pintype "output"))
    )
    (net (code "45") (name "/DBG_SWD") (class "Default")
      (node (ref "H4") (pin "8") (pinfunction "8_8") (pintype "unspecified"))
      (node (ref "U10") (pin "25") (pinfunction "SWD_25") (pintype "bidirectional"))
    )
    (net (code "46") (name "/DBG_VSYS") (class "Default")
      (node (ref "C25") (pin "2") (pinfunction "2_2") (pintype "unspecified"))
      (node (ref "D2") (pin "1") (pinfunction "K_1") (pintype "unspecified"))
      (node (ref "H4") (pin "2") (pinfunction "2_2") (pintype "unspecified"))
      (node (ref "R21") (pin "2") (pinfunction "2_2") (pintype "input"))
      (node (ref "U8") (pin "1") (pinfunction "VIN_1") (pintype "unspecified"))
    )
    (net (code "47") (name "/DBG_XIN") (class "Default")
      (node (ref "C27") (pin "2") (pinfunction "2_2") (pintype "input"))
      (node (ref "U10") (pin "20") (pinfunction "XIN_20") (pintype "input"))
      (node (ref "U9") (pin "1") (pinfunction "1_1") (pintype "input"))
    )
    (net (code "48") (name "/DBG_XOUT") (class "Default")
      (node (ref "R22") (pin "2") (pinfunction "2_2") (pintype "input"))
      (node (ref "U10") (pin "21") (pinfunction "XOUT_21") (pintype "unspecified"))
    )
    (net (code "49") (name "/GPIO0") (class "Default")
      (node (ref "J1") (pin "1") (pinfunction "1_1") (pintype "unspecified"))
      (node (ref "U1") (pin "2") (pinfunction "GPIO0_2") (pintype "bidirectional"))
    )
    (net (code "50") (name "/GPIO1") (class "Default")
      (node (ref "J1") (pin "2") (pinfunction "2_2") (pintype "unspecified"))
      (node (ref "U1") (pin "3") (pinfunction "GPIO1_3") (pintype "bidirectional"))
    )
    (net (code "51") (name "/GPIO2") (class "Default")
      (node (ref "J1") (pin "4") (pinfunction "4_4") (pintype "unspecified"))
      (node (ref "U1") (pin "4") (pinfunction "GPIO2_4") (pintype "bidirectional"))
    )
    (net (code "52") (name "/GPIO3") (class "Default")
      (node (ref "J1") (pin "5") (pinfunction "5_5") (pintype "unspecified"))
      (node (ref "U1") (pin "5") (pinfunction "GPIO3_5") (pintype "bidirectional"))
    )
    (net (code "53") (name "/GPIO4") (class "Default")
      (node (ref "J1") (pin "6") (pinfunction "6_6") (pintype "unspecified"))
      (node (ref "U1") (pin "6") (pinfunction "GPIO4_6") (pintype "bidirectional"))
    )
    (net (code "54") (name "/GPIO5") (class "Default")
      (node (ref "J1") (pin "7") (pinfunction "7_7") (pintype "unspecified"))
      (node (ref "U1") (pin "7") (pinfunction "GPIO5_7") (pintype "bidirectional"))
    )
    (net (code "55") (name "/GPIO6") (class "Default")
      (node (ref "J1") (pin "9") (pinfunction "9_9") (pintype "unspecified"))
      (node (ref "U1") (pin "8") (pinfunction "GPIO6_8") (pintype "bidirectional"))
    )
    (net (code "56") (name "/GPIO7") (class "Default")
      (node (ref "J1") (pin "10") (pinfunction "10_10") (pintype "unspecified"))
      (node (ref "U1") (pin "9") (pinfunction "GPIO7_9") (pintype "bidirectional"))
    )
    (net (code "57") (name "/GPIO8") (class "Default")
      (node (ref "J1") (pin "11") (pinfunction "11_11") (pintype "unspecified"))
      (node (ref "U1") (pin "11") (pinfunction "GPIO8_11") (pintype "bidirectional"))
    )
    (net (code "58") (name "/GPIO9") (class "Default")
      (node (ref "J1") (pin "12") (pinfunction "12_12") (pintype "unspecified"))
      (node (ref "U1") (pin "12") (pinfunction "GPIO9_12") (pintype "bidirectional"))
    )
    (net (code "59") (name "/GPIO10") (class "Default")
      (node (ref "J1") (pin "14") (pinfunction "14_14") (pintype "unspecified"))
      (node (ref "U1") (pin "13") (pinfunction "GPIO10_13") (pintype "bidirectional"))
    )
    (net (code "60") (name "/GPIO11") (class "Default")
      (node (ref "J1") (pin "15") (pinfunction "15_15") (pintype "unspecified"))
      (node (ref "U1") (pin "14") (pinfunction "GPIO11_14") (pintype "bidirectional"))
    )
    (net (code "61") (name "/GPIO12") (class "Default")
      (node (ref "J1") (pin "16") (pinfunction "16_16") (pintype "unspecified"))
      (node (ref "SIM1") (pin "7") (pinfunction "DAT0_7") (pintype "unspecified"))
      (node (ref "U1") (pin "15") (pinfunction "GPIO12_15") (pintype "bidirectional"))
    )
    (net (code "62") (name "/GPIO13") (class "Default")
      (node (ref "J1") (pin "17") (pinfunction "17_17") (pintype "unspecified"))
      (node (ref "SIM1") (pin "2") (pinfunction "CD/DAT3_2") (pintype "unspecified"))
      (node (ref "U1") (pin "16") (pinfunction "GPIO13_16") (pintype "bidirectional"))
    )
    (net (code "63") (name "/GPIO14") (class "Default")
      (node (ref "J1") (pin "19") (pinfunction "19_19") (pintype "unspecified"))
      (node (ref "SIM1") (pin "5") (pinfunction "CLK_5") (pintype "unspecified"))
      (node (ref "U1") (pin "17") (pinfunction "GPIO14_17") (pintype "bidirectional"))
    )
    (net (code "64") (name "/GPIO15") (class "Default")
      (node (ref "J1") (pin "20") (pinfunction "20_20") (pintype "unspecified"))
      (node (ref "SIM1") (pin "3") (pinfunction "CMD_3") (pintype "unspecified"))
      (node (ref "U1") (pin "18") (pinfunction "GPIO15_18") (pintype "bidirectional"))
    )
    (net (code "65") (name "/GPIO16") (class "Default")
      (node (ref "H1") (pin "5") (pinfunction "5_5") (pintype "input"))
      (node (ref "H2") (pin "5") (pinfunction "5_5") (pintype "input"))
      (node (ref "J2") (pin "20") (pinfunction "20_20") (pintype "unspecified"))
      (node (ref "U1") (pin "27") (pinfunction "GPIO16_27") (pintype "bidirectional"))
      (node (ref "U10") (pin "7") (pinfunction "GPIO5_7") (pintype "bidirectional"))
    )
    (net (code "66") (name "/GPIO17") (class "Default")
      (node (ref "H1") (pin "6") (pinfunction "6_6") (pintype "input"))
      (node (ref "H2") (pin "6") (pinfunction "6_6") (pintype "input"))
      (node (ref "J2") (pin "19") (pinfunction "19_19") (pintype "unspecified"))
      (node (ref "U1") (pin "28") (pinfunction "GPIO17_28") (pintype "bidirectional"))
      (node (ref "U10") (pin "6") (pinfunction "GPIO4_6") (pintype "bidirectional"))
    )
    (net (code "67") (name "/GPIO18") (class "Default")
      (node (ref "J2") (pin "17") (pinfunction "17_17") (pintype "unspecified"))
      (node (ref "U1") (pin "29") (pinfunction "GPIO18_29") (pintype "bidirectional"))
    )
    (net (code "68") (name "/GPIO19") (class "Default")
      (node (ref "J2") (pin "16") (pinfunction "16_16") (pintype "unspecified"))
      (node (ref "U1") (pin "30") (pinfunction "GPIO19_30") (pintype "bidirectional"))
    )
    (net (code "69") (name "/GPIO20") (class "Default")
      (node (ref "J2") (pin "15") (pinfunction "15_15") (pintype "unspecified"))
      (node (ref "U1") (pin "31") (pinfunction "GPIO20_31") (pintype "bidirectional"))
    )
    (net (code "70") (name "/GPIO21") (class "Default")
      (node (ref "J2") (pin "14") (pinfunction "14_14") (pintype "unspecified"))
      (node (ref "U1") (pin "32") (pinfunction "GPIO21_32") (pintype "bidirectional"))
    )
    (net (code "71") (name "/GPIO22") (class "Default")
      (node (ref "J2") (pin "12") (pinfunction "12_12") (pintype "unspecified"))
      (node (ref "U1") (pin "34") (pinfunction "GPIO22_34") (pintype "bidirectional"))
    )
    (net (code "72") (name "/GPIO23") (class "Default")
      (node (ref "SIM1") (pin "11") (pinfunction "11_11") (pintype "unspecified"))
      (node (ref "U1") (pin "35") (pinfunction "GPIO23_35") (pintype "bidirectional"))
    )
    (net (code "73") (name "/GPIO24") (class "Default")
      (node (ref "R3") (pin "1") (pinfunction "1_1") (pintype "input"))
      (node (ref "R4") (pin "2") (pinfunction "2_2") (pintype "input"))
      (node (ref "U1") (pin "36") (pinfunction "GPIO24_36") (pintype "bidirectional"))
    )
    (net (code "74") (name "/GPIO25") (class "Default")
      (node (ref "R10") (pin "2") (pinfunction "2_2") (pintype "input"))
      (node (ref "U1") (pin "37") (pinfunction "GPIO25_37") (pintype "bidirectional"))
    )
    (net (code "75") (name "/GPIO26_ADC0") (class "Default")
      (node (ref "J2") (pin "10") (pinfunction "10_10") (pintype "unspecified"))
      (node (ref "U1") (pin "38") (pinfunction "GPIO26_ADC0_38") (pintype "bidirectional"))
    )
    (net (code "76") (name "/GPIO27_ADC1") (class "Default")
      (node (ref "J2") (pin "9") (pinfunction "9_9") (pintype "unspecified"))
      (node (ref "U1") (pin "39") (pinfunction "GPIO27_ADC1_39") (pintype "bidirectional"))
    )
    (net (code "77") (name "/GPIO28_ADC2") (class "Default")
      (node (ref "J2") (pin "7") (pinfunction "7_7") (pintype "unspecified"))
      (node (ref "U1") (pin "40") (pinfunction "GPIO28_ADC2_40") (pintype "bidirectional"))
    )
    (net (code "78") (name "/GPIO29_ADC3") (class "Default")
      (node (ref "Q1") (pin "2") (pinfunction "S_2") (pintype "unspecified"))
      (node (ref "U1") (pin "41") (pinfunction "GPIO29_ADC3_41") (pintype "bidirectional"))
    )
    (net (code "79") (name "/QSPI_SCLK") (class "Default")
      (node (ref "U1") (pin "52") (pinfunction "QSPI_SCLK_52") (pintype "output"))
      (node (ref "U4") (pin "6") (pinfunction "CLK_6") (pintype "unspecified"))
    )
    (net (code "80") (name "/QSPI_SD0") (class "Default")
      (node (ref "U1") (pin "53") (pinfunction "QSPI_SD0_53") (pintype "bidirectional"))
      (node (ref "U4") (pin "5") (pinfunction "DI/IO0_5") (pintype "unspecified"))
    )
    (net (code "81") (name "/QSPI_SD1") (class "Default")
      (node (ref "U1") (pin "55") (pinfunction "QSPI_SD1_55") (pintype "bidirectional"))
      (node (ref "U4") (pin "2") (pinfunction "DO/IO1_2") (pintype "unspecified"))
    )
    (net (code "82") (name "/QSPI_SD2") (class "Default")
      (node (ref "U1") (pin "54") (pinfunction "QSPI_SD2_54") (pintype "bidirectional"))
      (node (ref "U4") (pin "3") (pinfunction "#WP/IO2_3") (pintype "unspecified"))
    )
    (net (code "83") (name "/QSPI_SD3") (class "Default")
      (node (ref "U1") (pin "51") (pinfunction "QSPI_SD3_51") (pintype "bidirectional"))
      (node (ref "U4") (pin "7") (pinfunction "#HOLD-OR-#REST/IO3_7") (pintype "unspecified"))
    )
    (net (code "84") (name "/QSPI_SS") (class "Default")
      (node (ref "R11") (pin "1") (pinfunction "1_1") (pintype "input"))
      (node (ref "R12") (pin "1") (pinfunction "1_1") (pintype "input"))
      (node (ref "U1") (pin "56") (pinfunction "QSPI_SS_56") (pintype "bidirectional"))
      (node (ref "U4") (pin "1") (pinfunction "#CS_1") (pintype "unspecified"))
    )
    (net (code "85") (name "/RUN") (class "Default")
      (node (ref "J2") (pin "11") (pinfunction "11_11") (pintype "unspecified"))
      (node (ref "SW2") (pin "1") (pinfunction "1_1") (pintype "input"))
      (node (ref "SW2") (pin "2") (pinfunction "2_2") (pintype "input"))
      (node (ref "U1") (pin "26") (pinfunction "RUN_26") (pintype "input"))
    )
    (net (code "86") (name "/SWCLK") (class "Default")
      (node (ref "H1") (pin "2") (pinfunction "2_2") (pintype "input"))
      (node (ref "H2") (pin "2") (pinfunction "2_2") (pintype "input"))
      (node (ref "U1") (pin "24") (pinfunction "SWCLK_24") (pintype "output"))
      (node (ref "U10") (pin "4") (pinfunction "GPIO2_4") (pintype "bidirectional"))
    )
    (net (code "87") (name "/SWD") (class "Default")
      (node (ref "H1") (pin "4") (pinfunction "4_4") (pintype "input"))
      (node (ref "H2") (pin "4") (pinfunction "4_4") (pintype "input"))
      (node (ref "U1") (pin "25") (pinfunction "SWD_25") (pintype "bidirectional"))
      (node (ref "U10") (pin "5") (pinfunction "GPIO3_5") (pintype "bidirectional"))
    )
    (net (code "88") (name "/VBUS") (class "Default")
      (node (ref "D1") (pin "2") (pinfunction "A_2") (pintype "unspecified"))
      (node (ref "D2") (pin "2") (pinfunction "A_2") (pintype "unspecified"))
      (node (ref "H1") (pin "1") (pinfunction "1_1") (pintype "input"))
      (node (ref "H2") (pin "1") (pinfunction "1_1") (pintype "input"))
      (node (ref "H4") (pin "1") (pinfunction "1_1") (pintype "unspecified"))
      (node (ref "J2") (pin "1") (pinfunction "1_1") (pintype "unspecified"))
      (node (ref "R3") (pin "2") (pinfunction "2_2") (pintype "input"))
      (node (ref "U2") (pin "A4B9") (pinfunction "VBUS_A4B9") (pintype "unspecified"))
      (node (ref "U2") (pin "A9B4") (pinfunction "VBUS_A9B4") (pintype "unspecified"))
      (node (ref "U6") (pin "A4B9") (pinfunction "VBUS_A4B9") (pintype "unspecified"))
      (node (ref "U6") (pin "A9B4") (pinfunction "VBUS_A9B4") (pintype "unspecified"))
    )
    (net (code "89") (name "/VSYS") (class "Default")
      (node (ref "C1") (pin "2") (pinfunction "2_2") (pintype "unspecified"))
      (node (ref "D1") (pin "1") (pinfunction "K_1") (pintype "unspecified"))
      (node (ref "J2") (pin "2") (pinfunction "2_2") (pintype "unspecified"))
      (node (ref "R15") (pin "2") (pinfunction "2_2") (pintype "input"))
      (node (ref "R5") (pin "2") (pinfunction "2_2") (pintype "input"))
      (node (ref "U3") (pin "1") (pinfunction "VIN_1") (pintype "unspecified"))
    )
    (net (code "90") (name "/XIN") (class "Default")
      (node (ref "C19") (pin "2") (pinfunction "2_2") (pintype "input"))
      (node (ref "U1") (pin "20") (pinfunction "XIN_20") (pintype "input"))
      (node (ref "U5") (pin "1") (pinfunction "1_1") (pintype "input"))
    )
    (net (code "91") (name "/XOUT") (class "Default")
      (node (ref "R13") (pin "2") (pinfunction "2_2") (pintype "input"))
      (node (ref "U1") (pin "21") (pinfunction "XOUT_21") (pintype "unspecified"))
    )
    (net (code "92") (name "3V3") (class "Default")
      (node (ref "C10") (pin "2") (pinfunction "2_2") (pintype "unspecified"))
      (node (ref "C11") (pin "2") (pinfunction "2_2") (pintype "unspecified"))
      (node (ref "C12") (pin "2") (pinfunction "2_2") (pintype "unspecified"))
      (node (ref "C13") (pin "2") (pinfunction "2_2") (pintype "unspecified"))
      (node (ref "C16") (pin "2") (pinfunction "2_2") (pintype "unspecified"))
      (node (ref "C18") (pin "2") (pinfunction "2_2") (pintype "unspecified"))
      (node (ref "C2") (pin "2") (pinfunction "2_2") (pintype "unspecified"))
      (node (ref "C7") (pin "2") (pinfunction "2_2") (pintype "unspecified"))
      (node (ref "C8") (pin "2") (pinfunction "2_2") (pintype "unspecified"))
      (node (ref "C9") (pin "2") (pinfunction "2_2") (pintype "unspecified"))
      (node (ref "J2") (pin "5") (pinfunction "5_5") (pintype "unspecified"))
      (node (ref "Q1") (pin "1") (pinfunction "G_1") (pintype "unspecified"))
      (node (ref "R1") (pin "2") (pinfunction "2_2") (pintype "input"))
      (node (ref "R11") (pin "2") (pinfunction "2_2") (pintype "input"))
      (node (ref "SIM1") (pin "4") (pinfunction "VDD_4") (pintype "unspecified"))
      (node (ref "U1") (pin "1") (pinfunction "IOVDD_1") (pintype "bidirectional"))
      (node (ref "U1") (pin "10") (pinfunction "IOVDD_10") (pintype "bidirectional"))
      (node (ref "U1") (pin "22") (pinfunction "IOVDD_22") (pintype "bidirectional"))
      (node (ref "U1") (pin "33") (pinfunction "IOVDD_33") (pintype "bidirectional"))
      (node (ref "U1") (pin "42") (pinfunction "IOVDD_42") (pintype "bidirectional"))
      (node (ref "U1") (pin "44") (pinfunction "VREG_IN_44") (pintype "bidirectional"))
      (node (ref "U1") (pin "48") (pinfunction "USB_VDD_48") (pintype "bidirectional"))
      (node (ref "U1") (pin "49") (pinfunction "IOVDD_49") (pintype "bidirectional"))
      (node (ref "U3") (pin "5") (pinfunction "VOUT_5") (pintype "unspecified"))
      (node (ref "U4") (pin "8") (pinfunction "VCC_8") (pintype "unspecified"))
    )
    (net (code "93") (name "GND") (class "Default")
      (node (ref "C1") (pin "1") (pinfunction "1_1") (pintype "unspecified"))
      (node (ref "C10") (pin "1") (pinfunction "1_1") (pintype "unspecified"))
      (node (ref "C11") (pin "1") (pinfunction "1_1") (pintype "unspecified"))
      (node (ref "C12") (pin "1") (pinfunction "1_1") (pintype "unspecified"))
      (node (ref "C13") (pin "1") (pinfunction "1_1") (pintype "unspecified"))
      (node (ref "C16") (pin "1") (pinfunction "1_1") (pintype "unspecified"))
      (node (ref "C17") (pin "1") (pinfunction "1_1") (pintype "unspecified"))
      (node (ref "C18") (pin "1") (pinfunction "1_1") (pintype "unspecified"))
      (node (ref "C19") (pin "1") (pinfunction "1_1") (pintype "input"))
      (node (ref "C2") (pin "1") (pinfunction "1_1") (pintype "unspecified"))
      (node (ref "C20") (pin "1") (pinfunction "1_1") (pintype "input"))
      (node (ref "C21") (pin "1") (pinfunction "1_1") (pintype "input"))
      (node (ref "C22") (pin "1") (pinfunction "1_1") (pintype "unspecified"))
      (node (ref "C23") (pin "1") (pinfunction "1_1") (pintype "unspecified"))
      (node (ref "C24") (pin "1") (pinfunction "1_1") (pintype "unspecified"))
      (node (ref "C25") (pin "1") (pinfunction "1_1") (pintype "unspecified"))
      (node (ref "C26") (pin "1") (pinfunction "1_1") (pintype "input"))
      (node (ref "C27") (pin "1") (pinfunction "1_1") (pintype "input"))
      (node (ref "C28") (pin "1") (pinfunction "1_1") (pintype "unspecified"))
      (node (ref "C29") (pin "1") (pinfunction "1_1") (pintype "unspecified"))
      (node (ref "C3") (pin "1") (pinfunction "1_1") (pintype "unspecified"))
      (node (ref "C30") (pin "1") (pinfunction "1_1") (pintype "unspecified"))
      (node (ref "C31") (pin "1") (pinfunction "1_1") (pintype "unspecified"))
      (node (ref "C32") (pin "1") (pinfunction "1_1") (pintype "unspecified"))
      (node (ref "C33") (pin "1") (pinfunction "1_1") (pintype "unspecified"))
      (node (ref "C34") (pin "1") (pinfunction "1_1") (pintype "unspecified"))
      (node (ref "C35") (pin "1") (pinfunction "1_1") (pintype "unspecified"))
      (node (ref "C36") (pin "1") (pinfunction "1_1") (pintype "unspecified"))
      (node (ref "C37") (pin "1") (pinfunction "1_1") (pintype "unspecified"))
      (node (ref "C38") (pin "1") (pinfunction "1_1") (pintype "unspecified"))
      (node (ref "C4") (pin "1") (pinfunction "1_1") (pintype "unspecified"))
      (node (ref "C5") (pin "1") (pinfunction "1_1") (pintype "unspecified"))
      (node (ref "C7") (pin "1") (pinfunction "1_1") (pintype "unspecified"))
      (node (ref "C8") (pin "1") (pinfunction "1_1") (pintype "unspecified"))
      (node (ref "C9") (pin "1") (pinfunction "1_1") (pintype "unspecified"))
      (node (ref "H1") (pin "3") (pinfunction "3_3") (pintype "input"))
      (node (ref "H2") (pin "3") (pinfunction "3_3") (pintype "input"))
      (node (ref "H3") (pin "3") (pinfunction "3_3") (pintype "unspecified"))
      (node (ref "H3") (pin "6") (pinfunction "6_6") (pintype "unspecified"))
      (node (ref "H4") (pin "3") (pinfunction "3_3") (pintype "unspecified"))
      (node (ref "H4") (pin "9") (pinfunction "9_9") (pintype "unspecified"))
      (node (ref "J1") (pin "13") (pinfunction "13_13") (pintype "unspecified"))
      (node (ref "J1") (pin "18") (pinfunction "18_18") (pintype "unspecified"))
      (node (ref "J1") (pin "3") (pinfunction "3_3") (pintype "unspecified"))
      (node (ref "J1") (pin "8") (pinfunction "8_8") (pintype "unspecified"))
      (node (ref "J2") (pin "13") (pinfunction "13_13") (pintype "unspecified"))
      (node (ref "J2") (pin "18") (pinfunction "18_18") (pintype "unspecified"))
      (node (ref "J2") (pin "3") (pinfunction "3_3") (pintype "unspecified"))
      (node (ref "J2") (pin "8") (pinfunction "8_8") (pintype "unspecified"))
      (node (ref "LED1") (pin "1") (pinfunction "K_1") (pintype "unspecified"))
      (node (ref "LED2") (pin "1") (pinfunction "K_1") (pintype "unspecified"))
      (node (ref "R14") (pin "1") (pinfunction "1_1") (pintype "input"))
      (node (ref "R16") (pin "2") (pinfunction "2_2") (pintype "input"))
      (node (ref "R17") (pin "2") (pinfunction "2_2") (pintype "input"))
      (node (ref "R4") (pin "1") (pinfunction "1_1") (pintype "input"))
      (node (ref "R6") (pin "2") (pinfunction "2_2") (pintype "input"))
      (node (ref "R7") (pin "2") (pinfunction "2_2") (pintype "input"))
      (node (ref "SIM1") (pin "10") (pinfunction "10_10") (pintype "unspecified"))
      (node (ref "SIM1") (pin "12") (pinfunction "12_12") (pintype "unspecified"))
      (node (ref "SIM1") (pin "13") (pinfunction "13_13") (pintype "unspecified"))
      (node (ref "SIM1") (pin "14") (pinfunction "14_14") (pintype "unspecified"))
      (node (ref "SIM1") (pin "6") (pinfunction "VSS_6") (pintype "unspecified"))
      (node (ref "SIM1") (pin "9") (pinfunction "9_9") (pintype "unspecified"))
      (node (ref "SW1") (pin "3") (pinfunction "3_3") (pintype "input"))
      (node (ref "SW1") (pin "4") (pinfunction "4_4") (pintype "input"))
      (node (ref "SW2") (pin "3") (pinfunction "3_3") (pintype "input"))
      (node (ref "SW2") (pin "4") (pinfunction "4_4") (pintype "input"))
      (node (ref "SW3") (pin "3") (pinfunction "3_3") (pintype "input"))
      (node (ref "SW3") (pin "4") (pinfunction "4_4") (pintype "input"))
      (node (ref "SW4") (pin "3") (pinfunction "3_3") (pintype "input"))
      (node (ref "SW4") (pin "4") (pinfunction "4_4") (pintype "input"))
      (node (ref "U1") (pin "19") (pinfunction "TESTEN_19") (pintype "unspecified"))
      (node (ref "U1") (pin "57") (pinfunction "GND_57") (pintype "bidirectional"))
      (node (ref "U10") (pin "19") (pinfunction "TESTEN_19") (pintype "unspecified"))
      (node (ref "U10") (pin "57") (pinfunction "GND_57") (pintype "bidirectional"))
      (node (ref "U11") (pin "4") (pinfunction "GND_4") (pintype "unspecified"))
      (node (ref "U2") (pin "12") (pinfunction "12_12") (pintype "unspecified"))
      (node (ref "U2") (pin "13") (pinfunction "13_13") (pintype "unspecified"))
      (node (ref "U2") (pin "14") (pinfunction "14_14") (pintype "unspecified"))
      (node (ref "U2") (pin "15") (pinfunction "15_15") (pintype "unspecified"))
      (node (ref "U2") (pin "A12B1") (pinfunction "GND_A12B1") (pintype "unspecified"))
      (node (ref "U2") (pin "A1B12") (pinfunction "GND_A1B12") (pintype "unspecified"))
      (node (ref "U3") (pin "2") (pinfunction "GND_2") (pintype "unspecified"))
      (node (ref "U4") (pin "4") (pinfunction "GND_4") (pintype "unspecified"))
      (node (ref "U5") (pin "2") (pinfunction "GND_2") (pintype "input"))
      (node (ref "U5") (pin "4") (pinfunction "GND_4") (pintype "input"))
      (node (ref "U6") (pin "12") (pinfunction "12_12") (pintype "unspecified"))
      (node (ref "U6") (pin "13") (pinfunction "13_13") (pintype "unspecified"))
      (node (ref "U6") (pin "14") (pinfunction "14_14") (pintype "unspecified"))
      (node (ref "U6") (pin "15") (pinfunction "15_15") (pintype "unspecified"))
      (node (ref "U6") (pin "A12B1") (pinfunction "GND_A12B1") (pintype "unspecified"))
      (node (ref "U6") (pin "A1B12") (pinfunction "GND_A1B12") (pintype "unspecified"))
      (node (ref "U8") (pin "2") (pinfunction "GND_2") (pintype "unspecified"))
      (node (ref "U9") (pin "2") (pinfunction "GND_2") (pintype "input"))
      (node (ref "U9") (pin "4") (pinfunction "GND_4") (pintype "input"))
    )
    (net (code "94") (name "Net-(C20-Pad2)") (class "Default")
      (node (ref "C20") (pin "2") (pinfunction "2_2") (pintype "input"))
      (node (ref "R13") (pin "1") (pinfunction "1_1") (pintype "input"))
      (node (ref "U5") (pin "3") (pinfunction "3_3") (pintype "input"))
    )
    (net (code "95") (name "Net-(C26-Pad2)") (class "Default")
      (node (ref "C26") (pin "2") (pinfunction "2_2") (pintype "input"))
      (node (ref "R22") (pin "1") (pinfunction "1_1") (pintype "input"))
      (node (ref "U9") (pin "3") (pinfunction "3_3") (pintype "input"))
    )
    (net (code "96") (name "Net-(LED1-A)") (class "Default")
      (node (ref "LED1") (pin "2") (pinfunction "A_2") (pintype "unspecified"))
      (node (ref "R10") (pin "1") (pinfunction "1_1") (pintype "input"))
    )
    (net (code "97") (name "Net-(LED2-A)") (class "Default")
      (node (ref "LED2") (pin "2") (pinfunction "A_2") (pintype "unspecified"))
      (node (ref "R23") (pin "1") (pinfunction "1_1") (pintype "input"))
    )
    (net (code "98") (name "Net-(Q1-D)") (class "Default")
      (node (ref "C21") (pin "2") (pinfunction "2_2") (pintype "input"))
      (node (ref "Q1") (pin "3") (pinfunction "D_3") (pintype "unspecified"))
      (node (ref "R14") (pin "2") (pinfunction "2_2") (pintype "input"))
      (node (ref "R15") (pin "1") (pinfunction "1_1") (pintype "input"))
    )
    (net (code "99") (name "Net-(R12-Pad2)") (class "Default")
      (node (ref "R12") (pin "2") (pinfunction "2_2") (pintype "input"))
      (node (ref "SW1") (pin "1") (pinfunction "1_1") (pintype "input"))
      (node (ref "SW1") (pin "2") (pinfunction "2_2") (pintype "input"))
    )
    (net (code "100") (name "Net-(R18-Pad2)") (class "Default")
      (node (ref "R18") (pin "2") (pinfunction "2_2") (pintype "input"))
      (node (ref "SW3") (pin "2") (pinfunction "2_2") (pintype "input"))
    )
    (net (code "101") (name "Net-(U1-ADC_AVDD)") (class "Default")
      (node (ref "C17") (pin "2") (pinfunction "2_2") (pintype "unspecified"))
      (node (ref "R2") (pin "1") (pinfunction "1_1") (pintype "input"))
      (node (ref "U1") (pin "43") (pinfunction "ADC_AVDD_43") (pintype "bidirectional"))
    )
    (net (code "102") (name "Net-(U1-USB_DM)") (class "Default")
      (node (ref "R9") (pin "1") (pinfunction "1_1") (pintype "input"))
      (node (ref "U1") (pin "46") (pinfunction "USB_DM_46") (pintype "bidirectional"))
    )
    (net (code "103") (name "Net-(U1-USB_DP)") (class "Default")
      (node (ref "R8") (pin "1") (pinfunction "1_1") (pintype "input"))
      (node (ref "U1") (pin "47") (pinfunction "USB_DP_47") (pintype "bidirectional"))
    )
    (net (code "104") (name "Net-(U2-CC1)") (class "Default")
      (node (ref "R6") (pin "1") (pinfunction "1_1") (pintype "input"))
      (node (ref "U2") (pin "A5") (pinfunction "CC1_A5") (pintype "unspecified"))
    )
    (net (code "105") (name "Net-(U2-CC2)") (class "Default")
      (node (ref "R7") (pin "1") (pinfunction "1_1") (pintype "input"))
      (node (ref "U2") (pin "B5") (pinfunction "CC2_B5") (pintype "unspecified"))
    )
    (net (code "106") (name "Net-(U6-CC1)") (class "Default")
      (node (ref "R16") (pin "1") (pinfunction "1_1") (pintype "input"))
      (node (ref "U6") (pin "A5") (pinfunction "CC1_A5") (pintype "unspecified"))
    )
    (net (code "107") (name "Net-(U6-CC2)") (class "Default")
      (node (ref "R17") (pin "1") (pinfunction "1_1") (pintype "input"))
      (node (ref "U6") (pin "B5") (pinfunction "CC2_B5") (pintype "unspecified"))
    )
    (net (code "108") (name "Net-(U10-USB_DM)") (class "Default")
      (node (ref "R25") (pin "1") (pinfunction "1_1") (pintype "input"))
      (node (ref "U10") (pin "46") (pinfunction "USB_DM_46") (pintype "bidirectional"))
    )
    (net (code "109") (name "Net-(U10-USB_DP)") (class "Default")
      (node (ref "R26") (pin "1") (pinfunction "1_1") (pintype "input"))
      (node (ref "U10") (pin "47") (pinfunction "USB_DP_47") (pintype "bidirectional"))
    )
    (net (code "110") (name "unconnected-(SIM1-DAT1-Pad8)") (class "Default")
      (node (ref "SIM1") (pin "8") (pinfunction "DAT1_8") (pintype "unspecified+no_connect"))
    )
    (net (code "111") (name "unconnected-(SIM1-DAT2-Pad1)") (class "Default")
      (node (ref "SIM1") (pin "1") (pinfunction "DAT2_1") (pintype "unspecified+no_connect"))
    )
    (net (code "112") (name "unconnected-(SW3-Pad1)") (class "Default")
      (node (ref "SW3") (pin "1") (pinfunction "1_1") (pintype "input+no_connect"))
    )
    (net (code "113") (name "unconnected-(SW4-Pad2)") (class "Default")
      (node (ref "SW4") (pin "2") (pinfunction "2_2") (pintype "input+no_connect"))
    )
    (net (code "114") (name "unconnected-(U2-SBU1-PadA8)") (class "Default")
      (node (ref "U2") (pin "A8") (pinfunction "SBU1_A8") (pintype "unspecified+no_connect"))
    )
    (net (code "115") (name "unconnected-(U2-SBU2-PadB8)") (class "Default")
      (node (ref "U2") (pin "B8") (pinfunction "SBU2_B8") (pintype "unspecified+no_connect"))
    )
    (net (code "116") (name "unconnected-(U3-NC-Pad4)") (class "Default")
      (node (ref "U3") (pin "4") (pinfunction "NC_4") (pintype "unspecified+no_connect"))
    )
    (net (code "117") (name "unconnected-(U4-EP-Pad9)") (class "Default")
      (node (ref "U4") (pin "9") (pinfunction "EP_9") (pintype "unspecified+no_connect"))
    )
    (net (code "118") (name "unconnected-(U6-SBU1-PadA8)") (class "Default")
      (node (ref "U6") (pin "A8") (pinfunction "SBU1_A8") (pintype "unspecified+no_connect"))
    )
    (net (code "119") (name "unconnected-(U6-SBU2-PadB8)") (class "Default")
      (node (ref "U6") (pin "B8") (pinfunction "SBU2_B8") (pintype "unspecified+no_connect"))
    )
    (net (code "120") (name "unconnected-(U8-NC-Pad4)") (class "Default")
      (node (ref "U8") (pin "4") (pinfunction "NC_4") (pintype "unspecified+no_connect"))
    )
    (net (code "121") (name "unconnected-(U11-EP-Pad9)") (class "Default")
      (node (ref "U11") (pin "9") (pinfunction "EP_9") (pintype "unspecified+no_connect"))
    )
  )
)
